# Current_Sense.net
KiCad netlist of a schematic drawn in Altium Designer
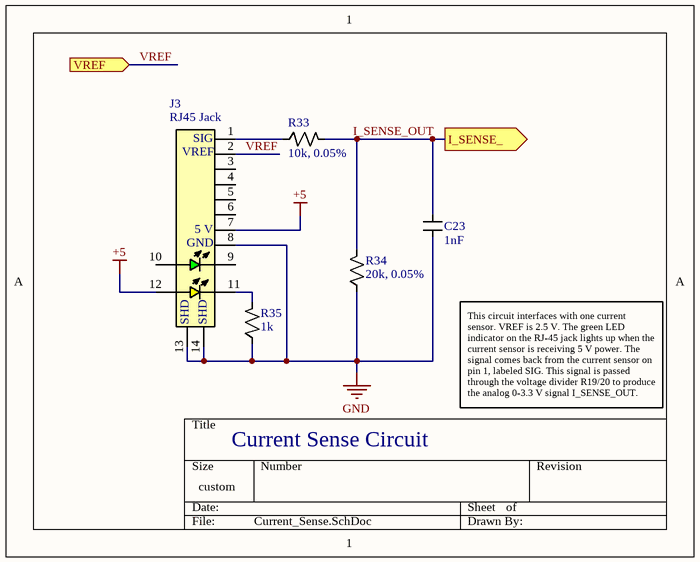
[diagram p0: Current_Sense.SchDoc]

(export (version "E")
  (design (tool "Eeschema 10.0.6"))
  (components
    (comp (ref "C23")
      (value "1nF")
      (footprint "0603_CAP")
      (description "Capacitor SMD MLCC 1 nF 0603")
      (libsource (lib "Load_Bank_New_IntLib") (part "C_1nF_0603"))
    )
    (comp (ref "J3")
      (value "RJ45 Jack")
      (footprint "RJ45_JACK")
      (description "Jack RJ-45 8-pin (for current sensing)")
      (libsource (lib "Load_Bank_New_IntLib") (part "J_RJ45_Jack_Sense"))
    )
    (comp (ref "R33")
      (value "10k, 0.05%")
      (footprint "0603_RES")
      (description "Resistor 10 kOhm 0603 0.05%")
      (libsource (lib "Load_Bank_New_IntLib") (part "R_10kOhm_0603_0.05%"))
    )
    (comp (ref "R34")
      (value "20k, 0.05%")
      (footprint "0603_RES")
      (description "Resistor 20 kOhm 0603 0.05%")
      (libsource (lib "Load_Bank_New_IntLib") (part "R_20kOhm_0603_0.05%"))
    )
    (comp (ref "R35")
      (value "1k")
      (footprint "0603_RES")
      (description "Resistor 1 kOhm 0603 0.5%")
      (libsource (lib "Load_Bank_New_IntLib") (part "R_1kOhm_0603_0.5%"))
    )
  )
  (nets
    (net (code "1") (name "+5") (class "Default")
      (node (ref "J3") (pin "12") (pintype "passive"))
      (node (ref "J3") (pin "7") (pinfunction "12_V_7") (pintype "passive"))
    )
    (net (code "2") (name "/I_SENSE_OUT") (class "Default")
      (node (ref "C23") (pin "2") (pintype "passive"))
      (node (ref "R33") (pin "2") (pintype "passive"))
      (node (ref "R34") (pin "2") (pintype "passive"))
    )
    (net (code "3") (name "/VREF") (class "Default")
      (node (ref "J3") (pin "2") (pinfunction "VREF_2") (pintype "passive"))
    )
    (net (code "4") (name "GND") (class "Default")
      (node (ref "C23") (pin "1") (pintype "passive"))
      (node (ref "J3") (pin "13") (pinfunction "SHD1_13") (pintype "passive"))
      (node (ref "J3") (pin "14") (pinfunction "SHD2_14") (pintype "passive"))
      (node (ref "J3") (pin "8") (pinfunction "GND_8") (pintype "passive"))
      (node (ref "R34") (pin "1") (pintype "passive"))
      (node (ref "R35") (pin "1") (pintype "passive"))
    )
    (net (code "5") (name "Net-(J3-Pad11)") (class "Default")
      (node (ref "J3") (pin "11") (pintype "passive"))
      (node (ref "R35") (pin "2") (pintype "passive"))
    )
    (net (code "6") (name "Net-(J3-Sig1)") (class "Default")
      (node (ref "J3") (pin "1") (pinfunction "Sig1_1") (pintype "passive"))
      (node (ref "R33") (pin "1") (pintype "passive"))
    )
    (net (code "7") (name "unconnected-(J3-NC-Pad3)") (class "Default")
      (node (ref "J3") (pin "3") (pinfunction "NC_3") (pintype "passive"))
    )
    (net (code "8") (name "unconnected-(J3-NC-Pad4)") (class "Default")
      (node (ref "J3") (pin "4") (pinfunction "NC_4") (pintype "passive"))
    )
    (net (code "9") (name "unconnected-(J3-NC-Pad5)") (class "Default")
      (node (ref "J3") (pin "5") (pinfunction "NC_5") (pintype "passive"))
    )
    (net (code "10") (name "unconnected-(J3-NC-Pad6)") (class "Default")
      (node (ref "J3") (pin "6") (pinfunction "NC_6") (pintype "passive"))
    )
    (net (code "11") (name "unconnected-(J3-Pad9)") (class "Default")
      (node (ref "J3") (pin "9") (pintype "passive"))
    )
    (net (code "12") (name "unconnected-(J3-Pad10)") (class "Default")
      (node (ref "J3") (pin "10") (pintype "passive"))
    )
  )
)
